# synchronous-demodulator.net
KiCad netlist of a schematic drawn in Altium Designer
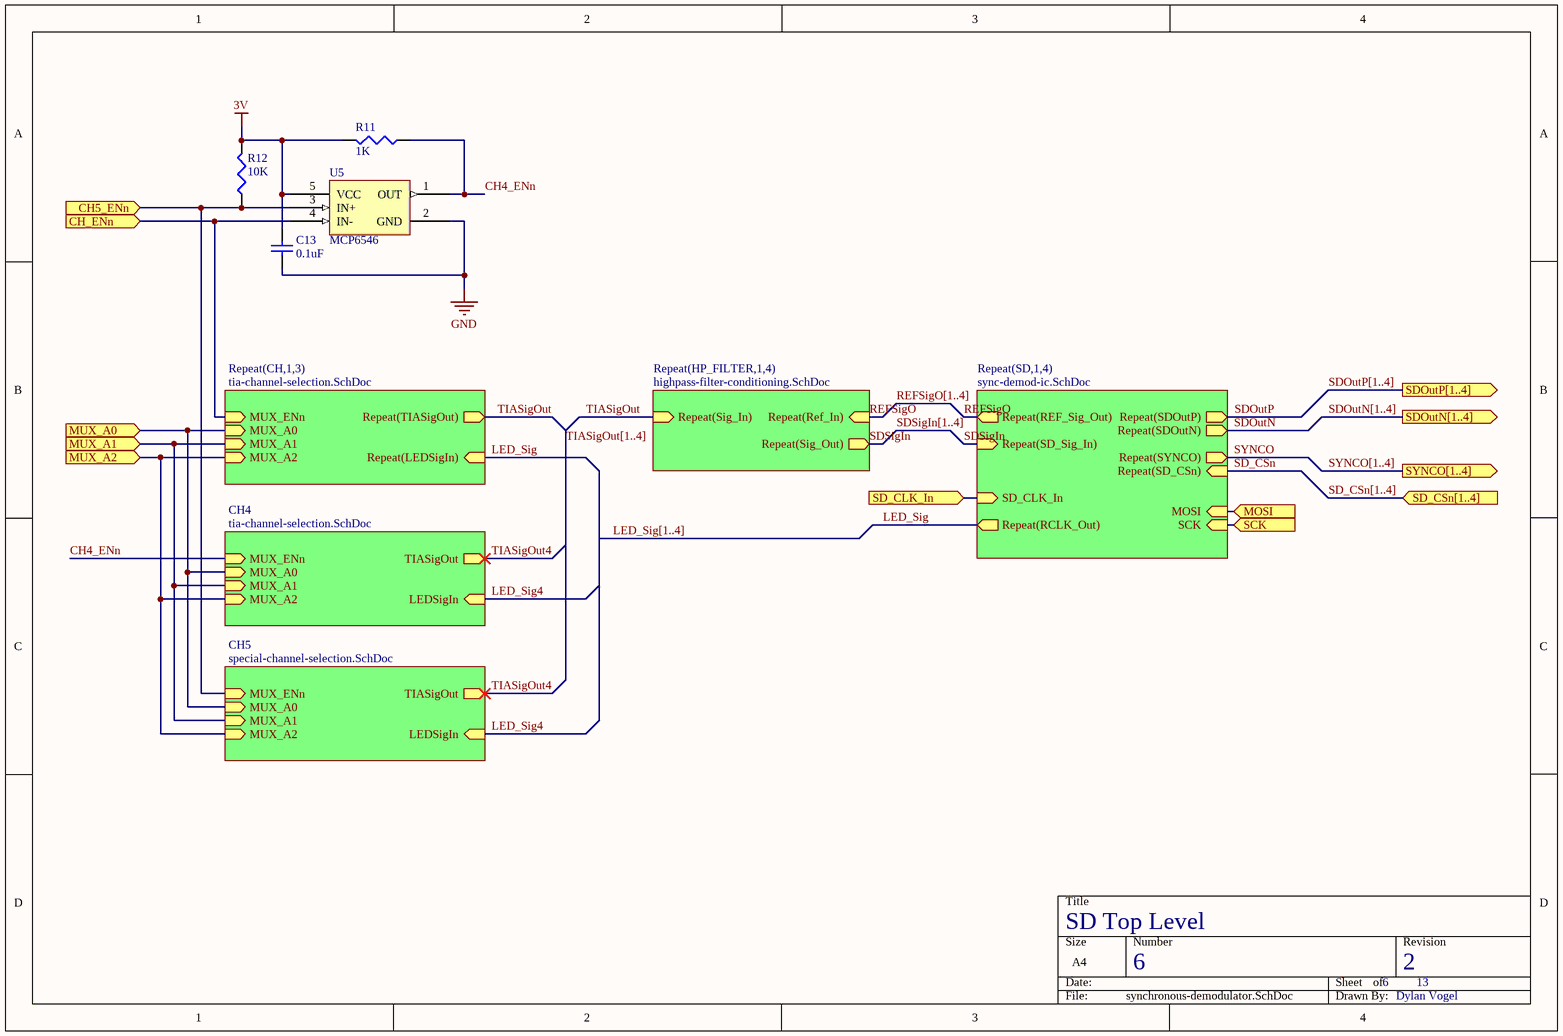
[diagram p0: synchronous-demodulator.SchDoc]

(export (version "E")
  (design (tool "Eeschema 10.0.6"))
  (components
    (comp (ref "C13")
      (value "0.1uF")
      (footprint "0402")
      (description "Capacitor (Semiconductor SIM Model)")
      (fields (field (name "PUBLISHER") "Altium Limited"))
      (libsource (lib "Miscellaneous Devices") (part "Cap Semi"))
    )
    (comp (ref "R11")
      (value "1K")
      (footprint "0402")
      (description "Resistor")
      (fields (field (name "PUBLISHER") "Altium Limited"))
      (libsource (lib "Miscellaneous Devices") (part "Res3"))
    )
    (comp (ref "R12")
      (value "10K")
      (footprint "0402")
      (description "Resistor")
      (fields (field (name "PUBLISHER") "Altium Limited"))
      (libsource (lib "Miscellaneous Devices") (part "Res3"))
    )
    (comp (ref "U5")
      (value "MCP6546")
      (footprint "SOT-23-5_95P290X160-5N")
      (description "Open-drain output sub-microamp comparator.")
      (libsource (lib "PAY") (part "MCP6546"))
    )
  )
  (nets
    (net (code "31") (name "/CH4_ENn") (class "Default")
      (node (ref "R11") (pin "1") (pinfunction "1_1") (pintype "passive"))
      (node (ref "U5") (pin "1") (pinfunction "OUT_1") (pintype "output"))
    )
    (net (code "32") (name "/CH5_ENn") (class "Default")
      (node (ref "R12") (pin "1") (pinfunction "1_1") (pintype "passive"))
      (node (ref "U5") (pin "3") (pinfunction "IN+_3") (pintype "input"))
    )
    (net (code "33") (name "/CH_ENn") (class "Default")
      (node (ref "U5") (pin "4") (pinfunction "IN-_4") (pintype "input"))
    )
    (net (code "58") (name "3V") (class "Default")
      (node (ref "C13") (pin "2") (pinfunction "2_2") (pintype "passive"))
      (node (ref "R11") (pin "2") (pinfunction "2_2") (pintype "passive"))
      (node (ref "R12") (pin "2") (pinfunction "2_2") (pintype "passive"))
      (node (ref "U5") (pin "5") (pinfunction "VCC_5") (pintype "power_in"))
    )
    (net (code "59") (name "GND") (class "Default")
      (node (ref "C13") (pin "1") (pinfunction "1_1") (pintype "passive"))
      (node (ref "U5") (pin "2") (pinfunction "GND_2") (pintype "power_in"))
    )
  )
)
